# SCRIPPS_new_board.net
KiCad netlist of a schematic drawn in EAGLE
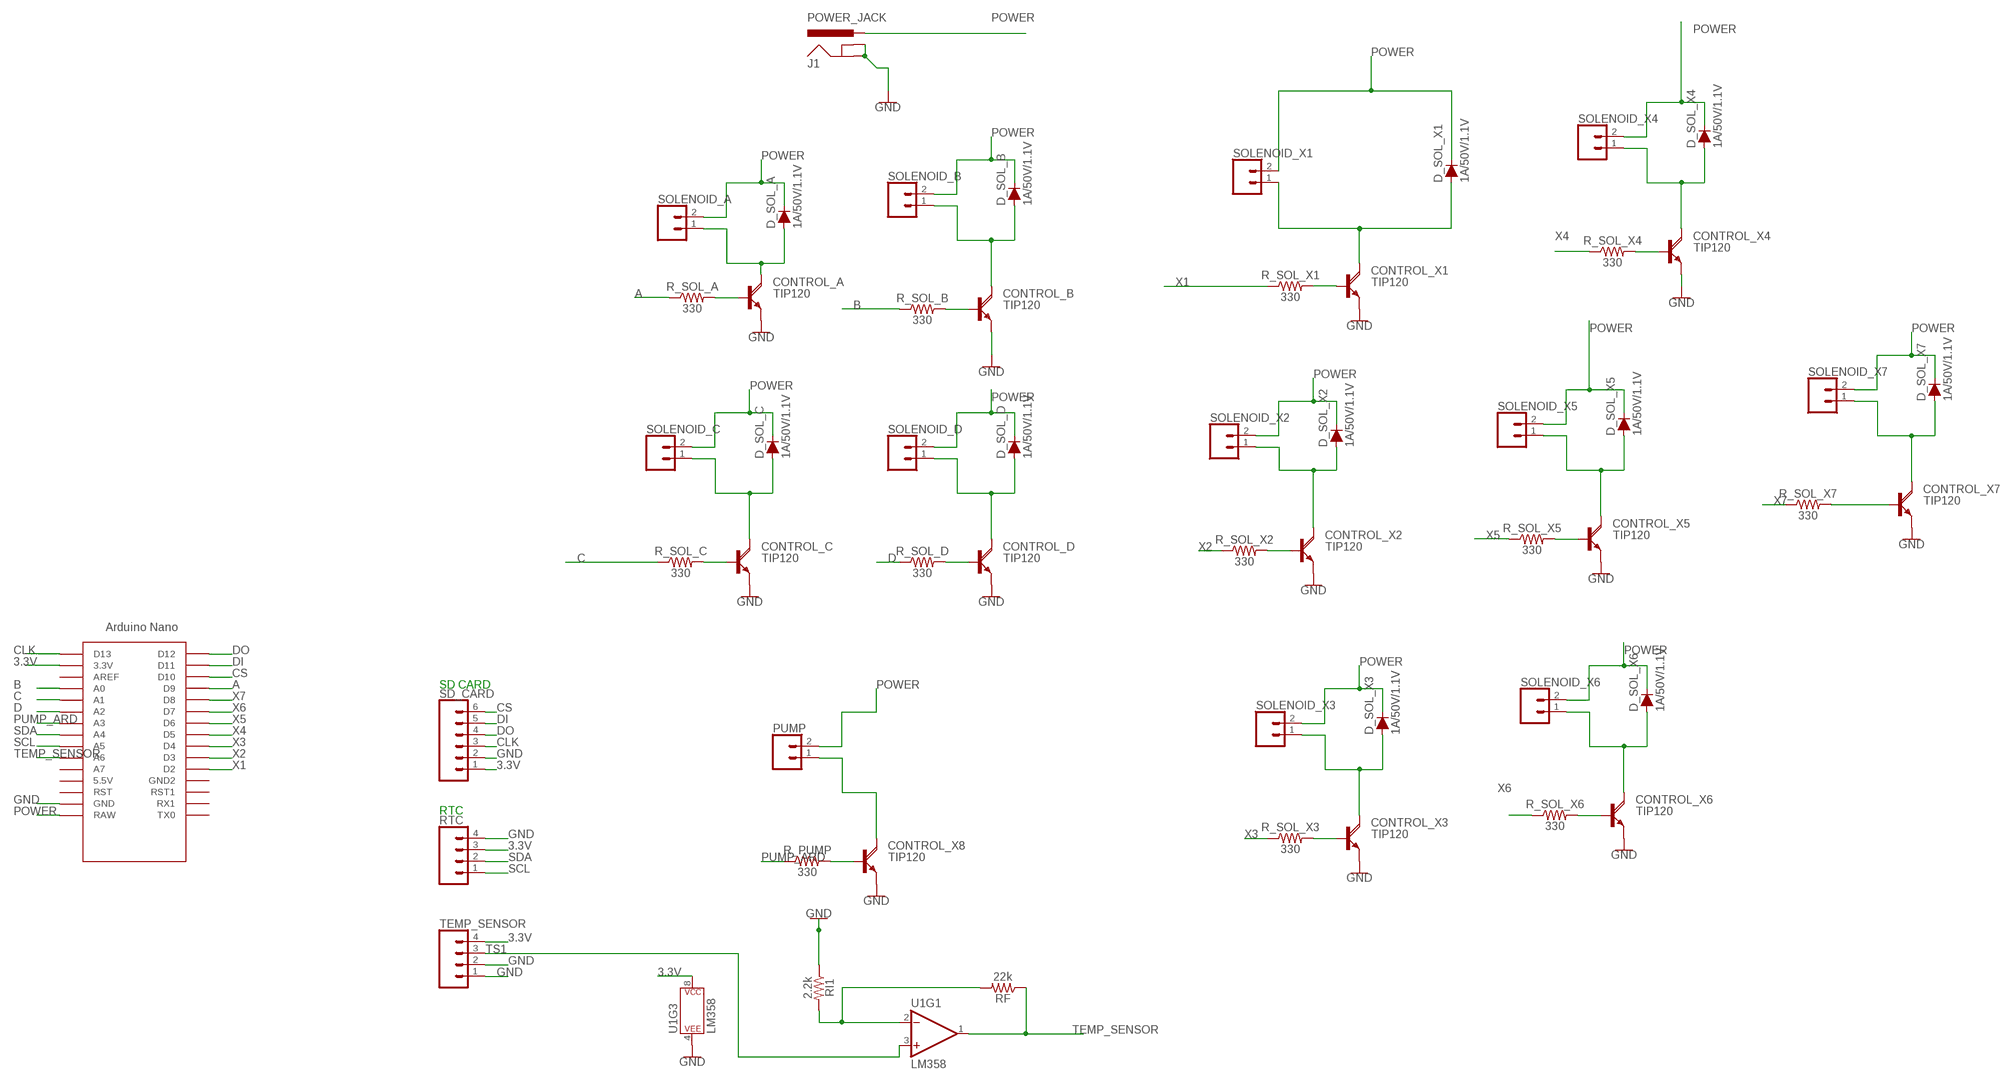
[diagram p0: schematic, sheet 1]

(export (version "E")
  (design (tool "Eeschema 10.0.6"))
  (components
    (comp (ref "CONTROL_A")
      (value "TIP120")
      (footprint "eagle-import:TO220AH")
      (libsource (lib "eagle-import") (part "TIP120"))
    )
    (comp (ref "CONTROL_B")
      (value "TIP120")
      (footprint "eagle-import:TO220AH")
      (libsource (lib "eagle-import") (part "TIP120"))
    )
    (comp (ref "CONTROL_C")
      (value "TIP120")
      (footprint "eagle-import:TO220AH")
      (libsource (lib "eagle-import") (part "TIP120"))
    )
    (comp (ref "CONTROL_D")
      (value "TIP120")
      (footprint "eagle-import:TO220AH")
      (libsource (lib "eagle-import") (part "TIP120"))
    )
    (comp (ref "CONTROL_X1")
      (value "TIP120")
      (footprint "eagle-import:TO220AH")
      (libsource (lib "eagle-import") (part "TIP120"))
    )
    (comp (ref "CONTROL_X2")
      (value "TIP120")
      (footprint "eagle-import:TO220AH")
      (libsource (lib "eagle-import") (part "TIP120"))
    )
    (comp (ref "CONTROL_X3")
      (value "TIP120")
      (footprint "eagle-import:TO220AH")
      (libsource (lib "eagle-import") (part "TIP120"))
    )
    (comp (ref "CONTROL_X4")
      (value "TIP120")
      (footprint "eagle-import:TO220AH")
      (libsource (lib "eagle-import") (part "TIP120"))
    )
    (comp (ref "CONTROL_X5")
      (value "TIP120")
      (footprint "eagle-import:TO220AH")
      (libsource (lib "eagle-import") (part "TIP120"))
    )
    (comp (ref "CONTROL_X6")
      (value "TIP120")
      (footprint "eagle-import:TO220AH")
      (libsource (lib "eagle-import") (part "TIP120"))
    )
    (comp (ref "CONTROL_X7")
      (value "TIP120")
      (footprint "eagle-import:TO220AH")
      (libsource (lib "eagle-import") (part "TIP120"))
    )
    (comp (ref "CONTROL_X8")
      (value "TIP120")
      (footprint "eagle-import:TO220AH")
      (libsource (lib "eagle-import") (part "TIP120"))
    )
    (comp (ref "D_SOL_A")
      (value "1A/50V/1.1V")
      (footprint "eagle-import:DIODE-1N4001")
      (libsource (lib "eagle-import") (part "DIODE-PTH"))
    )
    (comp (ref "D_SOL_B")
      (value "1A/50V/1.1V")
      (footprint "eagle-import:DIODE-1N4001")
      (libsource (lib "eagle-import") (part "DIODE-PTH"))
    )
    (comp (ref "D_SOL_C")
      (value "1A/50V/1.1V")
      (footprint "eagle-import:DIODE-1N4001")
      (libsource (lib "eagle-import") (part "DIODE-PTH"))
    )
    (comp (ref "D_SOL_D")
      (value "1A/50V/1.1V")
      (footprint "eagle-import:DIODE-1N4001")
      (libsource (lib "eagle-import") (part "DIODE-PTH"))
    )
    (comp (ref "D_SOL_X1")
      (value "1A/50V/1.1V")
      (footprint "eagle-import:DIODE-1N4001")
      (libsource (lib "eagle-import") (part "DIODE-PTH"))
    )
    (comp (ref "D_SOL_X2")
      (value "1A/50V/1.1V")
      (footprint "eagle-import:DIODE-1N4001")
      (libsource (lib "eagle-import") (part "DIODE-PTH"))
    )
    (comp (ref "D_SOL_X3")
      (value "1A/50V/1.1V")
      (footprint "eagle-import:DIODE-1N4001")
      (libsource (lib "eagle-import") (part "DIODE-PTH"))
    )
    (comp (ref "D_SOL_X4")
      (value "1A/50V/1.1V")
      (footprint "eagle-import:DIODE-1N4001")
      (libsource (lib "eagle-import") (part "DIODE-PTH"))
    )
    (comp (ref "D_SOL_X5")
      (value "1A/50V/1.1V")
      (footprint "eagle-import:DIODE-1N4001")
      (libsource (lib "eagle-import") (part "DIODE-PTH"))
    )
    (comp (ref "D_SOL_X6")
      (value "1A/50V/1.1V")
      (footprint "eagle-import:DIODE-1N4001")
      (libsource (lib "eagle-import") (part "DIODE-PTH"))
    )
    (comp (ref "D_SOL_X7")
      (value "1A/50V/1.1V")
      (footprint "eagle-import:DIODE-1N4001")
      (libsource (lib "eagle-import") (part "DIODE-PTH"))
    )
    (comp (ref "J1")
      (value "POWER_JACK")
      (footprint "eagle-import:POWER_JACK_PTH")
      (libsource (lib "eagle-import") (part "POWER_JACK"))
    )
    (comp (ref "PUMP")
      (value "CONN_02")
      (footprint "eagle-import:1X02")
      (libsource (lib "eagle-import") (part "CONN_02"))
    )
    (comp (ref "RF")
      (value "22k")
      (footprint "eagle-import:AXIAL-0.3")
      (libsource (lib "eagle-import") (part "330OHM-HORIZ-1/10W-5%"))
    )
    (comp (ref "RI1")
      (value "2.2k")
      (footprint "eagle-import:AXIAL-0.3")
      (libsource (lib "eagle-import") (part "330OHM-HORIZ-1/10W-5%"))
    )
    (comp (ref "RTC")
      (value "CONN_04")
      (footprint "eagle-import:1X04")
      (libsource (lib "eagle-import") (part "CONN_04"))
    )
    (comp (ref "R_PUMP")
      (value "330")
      (footprint "eagle-import:AXIAL-0.3")
      (libsource (lib "eagle-import") (part "330OHM-HORIZ-1/10W-5%"))
    )
    (comp (ref "R_SOL_A")
      (value "330")
      (footprint "eagle-import:AXIAL-0.3")
      (libsource (lib "eagle-import") (part "330OHM-HORIZ-1/10W-5%"))
    )
    (comp (ref "R_SOL_B")
      (value "330")
      (footprint "eagle-import:AXIAL-0.3")
      (libsource (lib "eagle-import") (part "330OHM-HORIZ-1/10W-5%"))
    )
    (comp (ref "R_SOL_C")
      (value "330")
      (footprint "eagle-import:AXIAL-0.3")
      (libsource (lib "eagle-import") (part "330OHM-HORIZ-1/10W-5%"))
    )
    (comp (ref "R_SOL_D")
      (value "330")
      (footprint "eagle-import:AXIAL-0.3")
      (libsource (lib "eagle-import") (part "330OHM-HORIZ-1/10W-5%"))
    )
    (comp (ref "R_SOL_X1")
      (value "330")
      (footprint "eagle-import:AXIAL-0.3")
      (libsource (lib "eagle-import") (part "330OHM-HORIZ-1/10W-5%"))
    )
    (comp (ref "R_SOL_X2")
      (value "330")
      (footprint "eagle-import:AXIAL-0.3")
      (libsource (lib "eagle-import") (part "330OHM-HORIZ-1/10W-5%"))
    )
    (comp (ref "R_SOL_X3")
      (value "330")
      (footprint "eagle-import:AXIAL-0.3")
      (libsource (lib "eagle-import") (part "330OHM-HORIZ-1/10W-5%"))
    )
    (comp (ref "R_SOL_X4")
      (value "330")
      (footprint "eagle-import:AXIAL-0.3")
      (libsource (lib "eagle-import") (part "330OHM-HORIZ-1/10W-5%"))
    )
    (comp (ref "R_SOL_X5")
      (value "330")
      (footprint "eagle-import:AXIAL-0.3")
      (libsource (lib "eagle-import") (part "330OHM-HORIZ-1/10W-5%"))
    )
    (comp (ref "R_SOL_X6")
      (value "330")
      (footprint "eagle-import:AXIAL-0.3")
      (libsource (lib "eagle-import") (part "330OHM-HORIZ-1/10W-5%"))
    )
    (comp (ref "R_SOL_X7")
      (value "330")
      (footprint "eagle-import:AXIAL-0.3")
      (libsource (lib "eagle-import") (part "330OHM-HORIZ-1/10W-5%"))
    )
    (comp (ref "SD_CARD")
      (value "CONN_06FEMALE_LOCK")
      (footprint "eagle-import:1X06_FEMALE_LOCK.010")
      (libsource (lib "eagle-import") (part "CONN_06FEMALE_LOCK"))
    )
    (comp (ref "SOLENOID_A")
      (value "CONN_02")
      (footprint "eagle-import:1X02")
      (libsource (lib "eagle-import") (part "CONN_02"))
    )
    (comp (ref "SOLENOID_B")
      (value "CONN_02")
      (footprint "eagle-import:1X02")
      (libsource (lib "eagle-import") (part "CONN_02"))
    )
    (comp (ref "SOLENOID_C")
      (value "CONN_02")
      (footprint "eagle-import:1X02")
      (libsource (lib "eagle-import") (part "CONN_02"))
    )
    (comp (ref "SOLENOID_D")
      (value "CONN_02")
      (footprint "eagle-import:1X02")
      (libsource (lib "eagle-import") (part "CONN_02"))
    )
    (comp (ref "SOLENOID_X1")
      (value "CONN_02")
      (footprint "eagle-import:1X02")
      (libsource (lib "eagle-import") (part "CONN_02"))
    )
    (comp (ref "SOLENOID_X2")
      (value "CONN_02")
      (footprint "eagle-import:1X02")
      (libsource (lib "eagle-import") (part "CONN_02"))
    )
    (comp (ref "SOLENOID_X3")
      (value "CONN_02")
      (footprint "eagle-import:1X02")
      (libsource (lib "eagle-import") (part "CONN_02"))
    )
    (comp (ref "SOLENOID_X4")
      (value "CONN_02")
      (footprint "eagle-import:1X02")
      (libsource (lib "eagle-import") (part "CONN_02"))
    )
    (comp (ref "SOLENOID_X5")
      (value "CONN_02")
      (footprint "eagle-import:1X02")
      (libsource (lib "eagle-import") (part "CONN_02"))
    )
    (comp (ref "SOLENOID_X6")
      (value "CONN_02")
      (footprint "eagle-import:1X02")
      (libsource (lib "eagle-import") (part "CONN_02"))
    )
    (comp (ref "SOLENOID_X7")
      (value "CONN_02")
      (footprint "eagle-import:1X02")
      (libsource (lib "eagle-import") (part "CONN_02"))
    )
    (comp (ref "TEMP_SENSOR")
      (value "CONN_04")
      (footprint "eagle-import:1X04")
      (libsource (lib "eagle-import") (part "CONN_04"))
    )
    (comp (ref "U$2")
      (value "NANO")
      (footprint "eagle-import:NANO")
      (libsource (lib "eagle-import") (part "NANO"))
    )
    (comp (ref "U1")
      (value "LM358")
      (footprint "eagle-import:DIP08")
      (libsource (lib "eagle-import") (part "LM358"))
    )
  )
  (nets
    (net (code "1") (name "/3.3V") (class "Default")
      (node (ref "RTC") (pin "3") (pinfunction "3_3") (pintype "passive"))
      (node (ref "SD_CARD") (pin "1") (pinfunction "1_1") (pintype "passive"))
      (node (ref "TEMP_SENSOR") (pin "4") (pinfunction "4_4") (pintype "passive"))
      (node (ref "U$2") (pin "3.3V") (pinfunction "3.3V_3.3V") (pintype "bidirectional"))
      (node (ref "U1") (pin "8") (pinfunction "P$V+_8") (pintype "bidirectional"))
    )
    (net (code "2") (name "/A") (class "Default")
      (node (ref "R_SOL_A") (pin "P$1") (pinfunction "1_P$1") (pintype "passive"))
      (node (ref "U$2") (pin "D9") (pinfunction "D9_D9") (pintype "bidirectional"))
    )
    (net (code "3") (name "/B") (class "Default")
      (node (ref "R_SOL_B") (pin "P$1") (pinfunction "1_P$1") (pintype "passive"))
      (node (ref "U$2") (pin "A0") (pinfunction "A0_A0") (pintype "bidirectional"))
    )
    (net (code "4") (name "/C") (class "Default")
      (node (ref "R_SOL_C") (pin "P$1") (pinfunction "1_P$1") (pintype "passive"))
      (node (ref "U$2") (pin "A1") (pinfunction "A1_A1") (pintype "bidirectional"))
    )
    (net (code "5") (name "/CLK") (class "Default")
      (node (ref "SD_CARD") (pin "3") (pinfunction "3_3") (pintype "passive"))
      (node (ref "U$2") (pin "D13") (pinfunction "D13_D13") (pintype "bidirectional"))
    )
    (net (code "6") (name "/CS") (class "Default")
      (node (ref "SD_CARD") (pin "6") (pinfunction "6_6") (pintype "passive"))
      (node (ref "U$2") (pin "D10") (pinfunction "D10_D10") (pintype "bidirectional"))
    )
    (net (code "7") (name "/D") (class "Default")
      (node (ref "R_SOL_D") (pin "P$1") (pinfunction "1_P$1") (pintype "passive"))
      (node (ref "U$2") (pin "A2") (pinfunction "A2_A2") (pintype "bidirectional"))
    )
    (net (code "8") (name "/DI") (class "Default")
      (node (ref "SD_CARD") (pin "5") (pinfunction "5_5") (pintype "passive"))
      (node (ref "U$2") (pin "D11") (pinfunction "D11_D11") (pintype "bidirectional"))
    )
    (net (code "9") (name "/DO") (class "Default")
      (node (ref "SD_CARD") (pin "4") (pinfunction "4_4") (pintype "passive"))
      (node (ref "U$2") (pin "D12") (pinfunction "D12_D12") (pintype "bidirectional"))
    )
    (net (code "10") (name "/POWER") (class "Default")
      (node (ref "D_SOL_A") (pin "C") (pinfunction "C_C") (pintype "passive"))
      (node (ref "D_SOL_B") (pin "C") (pinfunction "C_C") (pintype "passive"))
      (node (ref "D_SOL_C") (pin "C") (pinfunction "C_C") (pintype "passive"))
      (node (ref "D_SOL_D") (pin "C") (pinfunction "C_C") (pintype "passive"))
      (node (ref "D_SOL_X1") (pin "C") (pinfunction "C_C") (pintype "passive"))
      (node (ref "D_SOL_X2") (pin "C") (pinfunction "C_C") (pintype "passive"))
      (node (ref "D_SOL_X3") (pin "C") (pinfunction "C_C") (pintype "passive"))
      (node (ref "D_SOL_X4") (pin "C") (pinfunction "C_C") (pintype "passive"))
      (node (ref "D_SOL_X5") (pin "C") (pinfunction "C_C") (pintype "passive"))
      (node (ref "D_SOL_X6") (pin "C") (pinfunction "C_C") (pintype "passive"))
      (node (ref "D_SOL_X7") (pin "C") (pinfunction "C_C") (pintype "passive"))
      (node (ref "J1") (pin "PWR") (pinfunction "PWR_PWR") (pintype "bidirectional"))
      (node (ref "PUMP") (pin "2") (pinfunction "2_2") (pintype "passive"))
      (node (ref "SOLENOID_A") (pin "2") (pinfunction "2_2") (pintype "passive"))
      (node (ref "SOLENOID_B") (pin "2") (pinfunction "2_2") (pintype "passive"))
      (node (ref "SOLENOID_C") (pin "2") (pinfunction "2_2") (pintype "passive"))
      (node (ref "SOLENOID_D") (pin "2") (pinfunction "2_2") (pintype "passive"))
      (node (ref "SOLENOID_X1") (pin "2") (pinfunction "2_2") (pintype "passive"))
      (node (ref "SOLENOID_X2") (pin "2") (pinfunction "2_2") (pintype "passive"))
      (node (ref "SOLENOID_X3") (pin "2") (pinfunction "2_2") (pintype "passive"))
      (node (ref "SOLENOID_X4") (pin "2") (pinfunction "2_2") (pintype "passive"))
      (node (ref "SOLENOID_X5") (pin "2") (pinfunction "2_2") (pintype "passive"))
      (node (ref "SOLENOID_X6") (pin "2") (pinfunction "2_2") (pintype "passive"))
      (node (ref "SOLENOID_X7") (pin "2") (pinfunction "2_2") (pintype "passive"))
      (node (ref "U$2") (pin "RAW") (pinfunction "RAW_RAW") (pintype "bidirectional"))
    )
    (net (code "11") (name "/PUMP_ARD") (class "Default")
      (node (ref "R_PUMP") (pin "P$1") (pinfunction "1_P$1") (pintype "passive"))
      (node (ref "U$2") (pin "A3") (pinfunction "A3_A3") (pintype "bidirectional"))
    )
    (net (code "12") (name "/SCL") (class "Default")
      (node (ref "RTC") (pin "1") (pinfunction "1_1") (pintype "passive"))
      (node (ref "U$2") (pin "A5") (pinfunction "A5_A5") (pintype "bidirectional"))
    )
    (net (code "13") (name "/SDA") (class "Default")
      (node (ref "RTC") (pin "2") (pinfunction "2_2") (pintype "passive"))
      (node (ref "U$2") (pin "A4") (pinfunction "A4_A4") (pintype "bidirectional"))
    )
    (net (code "14") (name "/TEMP_SENSOR") (class "Default")
      (node (ref "RF") (pin "P$1") (pinfunction "1_P$1") (pintype "passive"))
      (node (ref "U$2") (pin "A6") (pinfunction "A6_A6") (pintype "bidirectional"))
      (node (ref "U1") (pin "1") (pinfunction "OUT_1") (pintype "output"))
    )
    (net (code "15") (name "/TS1") (class "Default")
      (node (ref "TEMP_SENSOR") (pin "3") (pinfunction "3_3") (pintype "passive"))
      (node (ref "U1") (pin "3") (pinfunction "+IN_3") (pintype "input"))
    )
    (net (code "16") (name "/X1") (class "Default")
      (node (ref "R_SOL_X1") (pin "P$1") (pinfunction "1_P$1") (pintype "passive"))
      (node (ref "U$2") (pin "D2") (pinfunction "D2_D2") (pintype "bidirectional"))
    )
    (net (code "17") (name "/X2") (class "Default")
      (node (ref "R_SOL_X2") (pin "P$1") (pinfunction "1_P$1") (pintype "passive"))
      (node (ref "U$2") (pin "D3") (pinfunction "D3_D3") (pintype "bidirectional"))
    )
    (net (code "18") (name "/X3") (class "Default")
      (node (ref "R_SOL_X3") (pin "P$1") (pinfunction "1_P$1") (pintype "passive"))
      (node (ref "U$2") (pin "D4") (pinfunction "D4_D4") (pintype "bidirectional"))
    )
    (net (code "19") (name "/X4") (class "Default")
      (node (ref "R_SOL_X4") (pin "P$1") (pinfunction "1_P$1") (pintype "passive"))
      (node (ref "U$2") (pin "D5") (pinfunction "D5_D5") (pintype "bidirectional"))
    )
    (net (code "20") (name "/X5") (class "Default")
      (node (ref "R_SOL_X5") (pin "P$1") (pinfunction "1_P$1") (pintype "passive"))
      (node (ref "U$2") (pin "D6") (pinfunction "D6_D6") (pintype "bidirectional"))
    )
    (net (code "21") (name "/X6") (class "Default")
      (node (ref "R_SOL_X6") (pin "P$1") (pinfunction "1_P$1") (pintype "passive"))
      (node (ref "U$2") (pin "D7") (pinfunction "D7_D7") (pintype "bidirectional"))
    )
    (net (code "22") (name "/X7") (class "Default")
      (node (ref "R_SOL_X7") (pin "P$1") (pinfunction "1_P$1") (pintype "passive"))
      (node (ref "U$2") (pin "D8") (pinfunction "D8_D8") (pintype "bidirectional"))
    )
    (net (code "23") (name "GND") (class "Default")
      (node (ref "CONTROL_A") (pin "E") (pinfunction "E_E") (pintype "passive"))
      (node (ref "CONTROL_B") (pin "E") (pinfunction "E_E") (pintype "passive"))
      (node (ref "CONTROL_C") (pin "E") (pinfunction "E_E") (pintype "passive"))
      (node (ref "CONTROL_D") (pin "E") (pinfunction "E_E") (pintype "passive"))
      (node (ref "CONTROL_X1") (pin "E") (pinfunction "E_E") (pintype "passive"))
      (node (ref "CONTROL_X2") (pin "E") (pinfunction "E_E") (pintype "passive"))
      (node (ref "CONTROL_X3") (pin "E") (pinfunction "E_E") (pintype "passive"))
      (node (ref "CONTROL_X4") (pin "E") (pinfunction "E_E") (pintype "passive"))
      (node (ref "CONTROL_X5") (pin "E") (pinfunction "E_E") (pintype "passive"))
      (node (ref "CONTROL_X6") (pin "E") (pinfunction "E_E") (pintype "passive"))
      (node (ref "CONTROL_X7") (pin "E") (pinfunction "E_E") (pintype "passive"))
      (node (ref "CONTROL_X8") (pin "E") (pinfunction "E_E") (pintype "passive"))
      (node (ref "J1") (pin "GND") (pinfunction "GND_GND") (pintype "bidirectional"))
      (node (ref "J1") (pin "GNDBREAK") (pinfunction "GNDBREAK_GNDBREAK") (pintype "bidirectional"))
      (node (ref "RI1") (pin "P$1") (pinfunction "1_P$1") (pintype "passive"))
      (node (ref "RTC") (pin "4") (pinfunction "4_4") (pintype "passive"))
      (node (ref "SD_CARD") (pin "2") (pinfunction "2_2") (pintype "passive"))
      (node (ref "TEMP_SENSOR") (pin "1") (pinfunction "1_1") (pintype "passive"))
      (node (ref "TEMP_SENSOR") (pin "2") (pinfunction "2_2") (pintype "passive"))
      (node (ref "U$2") (pin "GND") (pinfunction "GND_GND") (pintype "bidirectional"))
      (node (ref "U1") (pin "4") (pinfunction "P$V-_4") (pintype "bidirectional"))
    )
    (net (code "24") (name "Net-(CONTROL_A-PadC)") (class "Default")
      (node (ref "CONTROL_A") (pin "C") (pinfunction "C_C") (pintype "passive"))
      (node (ref "D_SOL_A") (pin "A") (pinfunction "A_A") (pintype "passive"))
      (node (ref "SOLENOID_A") (pin "1") (pinfunction "1_1") (pintype "passive"))
    )
    (net (code "25") (name "Net-(CONTROL_B-PadC)") (class "Default")
      (node (ref "CONTROL_B") (pin "C") (pinfunction "C_C") (pintype "passive"))
      (node (ref "D_SOL_B") (pin "A") (pinfunction "A_A") (pintype "passive"))
      (node (ref "SOLENOID_B") (pin "1") (pinfunction "1_1") (pintype "passive"))
    )
    (net (code "26") (name "Net-(CONTROL_C-PadC)") (class "Default")
      (node (ref "CONTROL_C") (pin "C") (pinfunction "C_C") (pintype "passive"))
      (node (ref "D_SOL_C") (pin "A") (pinfunction "A_A") (pintype "passive"))
      (node (ref "SOLENOID_C") (pin "1") (pinfunction "1_1") (pintype "passive"))
    )
    (net (code "27") (name "Net-(CONTROL_D-PadC)") (class "Default")
      (node (ref "CONTROL_D") (pin "C") (pinfunction "C_C") (pintype "passive"))
      (node (ref "D_SOL_D") (pin "A") (pinfunction "A_A") (pintype "passive"))
      (node (ref "SOLENOID_D") (pin "1") (pinfunction "1_1") (pintype "passive"))
    )
    (net (code "28") (name "Net-(CONTROL_X1-PadC)") (class "Default")
      (node (ref "CONTROL_X1") (pin "C") (pinfunction "C_C") (pintype "passive"))
      (node (ref "D_SOL_X1") (pin "A") (pinfunction "A_A") (pintype "passive"))
      (node (ref "SOLENOID_X1") (pin "1") (pinfunction "1_1") (pintype "passive"))
    )
    (net (code "29") (name "Net-(CONTROL_X2-PadC)") (class "Default")
      (node (ref "CONTROL_X2") (pin "C") (pinfunction "C_C") (pintype "passive"))
      (node (ref "D_SOL_X2") (pin "A") (pinfunction "A_A") (pintype "passive"))
      (node (ref "SOLENOID_X2") (pin "1") (pinfunction "1_1") (pintype "passive"))
    )
    (net (code "30") (name "Net-(CONTROL_X3-PadC)") (class "Default")
      (node (ref "CONTROL_X3") (pin "C") (pinfunction "C_C") (pintype "passive"))
      (node (ref "D_SOL_X3") (pin "A") (pinfunction "A_A") (pintype "passive"))
      (node (ref "SOLENOID_X3") (pin "1") (pinfunction "1_1") (pintype "passive"))
    )
    (net (code "31") (name "Net-(CONTROL_X4-PadC)") (class "Default")
      (node (ref "CONTROL_X4") (pin "C") (pinfunction "C_C") (pintype "passive"))
      (node (ref "D_SOL_X4") (pin "A") (pinfunction "A_A") (pintype "passive"))
      (node (ref "SOLENOID_X4") (pin "1") (pinfunction "1_1") (pintype "passive"))
    )
    (net (code "32") (name "Net-(CONTROL_X5-PadC)") (class "Default")
      (node (ref "CONTROL_X5") (pin "C") (pinfunction "C_C") (pintype "passive"))
      (node (ref "D_SOL_X5") (pin "A") (pinfunction "A_A") (pintype "passive"))
      (node (ref "SOLENOID_X5") (pin "1") (pinfunction "1_1") (pintype "passive"))
    )
    (net (code "33") (name "Net-(CONTROL_X6-PadC)") (class "Default")
      (node (ref "CONTROL_X6") (pin "C") (pinfunction "C_C") (pintype "passive"))
      (node (ref "D_SOL_X6") (pin "A") (pinfunction "A_A") (pintype "passive"))
      (node (ref "SOLENOID_X6") (pin "1") (pinfunction "1_1") (pintype "passive"))
    )
    (net (code "34") (name "Net-(CONTROL_X7-PadC)") (class "Default")
      (node (ref "CONTROL_X7") (pin "C") (pinfunction "C_C") (pintype "passive"))
      (node (ref "D_SOL_X7") (pin "A") (pinfunction "A_A") (pintype "passive"))
      (node (ref "SOLENOID_X7") (pin "1") (pinfunction "1_1") (pintype "passive"))
    )
    (net (code "35") (name "Net-(CONTROL_X8-PadC)") (class "Default")
      (node (ref "CONTROL_X8") (pin "C") (pinfunction "C_C") (pintype "passive"))
      (node (ref "PUMP") (pin "1") (pinfunction "1_1") (pintype "passive"))
    )
    (net (code "36") (name "Net-(RF-2)") (class "Default")
      (node (ref "RF") (pin "P$2") (pinfunction "2_P$2") (pintype "passive"))
      (node (ref "RI1") (pin "P$2") (pinfunction "2_P$2") (pintype "passive"))
      (node (ref "U1") (pin "2") (pinfunction "-IN_2") (pintype "input"))
    )
    (net (code "37") (name "Net-(R_PUMP-2)") (class "Default")
      (node (ref "CONTROL_X8") (pin "B") (pinfunction "B_B") (pintype "passive"))
      (node (ref "R_PUMP") (pin "P$2") (pinfunction "2_P$2") (pintype "passive"))
    )
    (net (code "38") (name "Net-(R_SOL_A-2)") (class "Default")
      (node (ref "CONTROL_A") (pin "B") (pinfunction "B_B") (pintype "passive"))
      (node (ref "R_SOL_A") (pin "P$2") (pinfunction "2_P$2") (pintype "passive"))
    )
    (net (code "39") (name "Net-(R_SOL_B-2)") (class "Default")
      (node (ref "CONTROL_B") (pin "B") (pinfunction "B_B") (pintype "passive"))
      (node (ref "R_SOL_B") (pin "P$2") (pinfunction "2_P$2") (pintype "passive"))
    )
    (net (code "40") (name "Net-(R_SOL_C-2)") (class "Default")
      (node (ref "CONTROL_C") (pin "B") (pinfunction "B_B") (pintype "passive"))
      (node (ref "R_SOL_C") (pin "P$2") (pinfunction "2_P$2") (pintype "passive"))
    )
    (net (code "41") (name "Net-(R_SOL_D-2)") (class "Default")
      (node (ref "CONTROL_D") (pin "B") (pinfunction "B_B") (pintype "passive"))
      (node (ref "R_SOL_D") (pin "P$2") (pinfunction "2_P$2") (pintype "passive"))
    )
    (net (code "42") (name "Net-(R_SOL_X1-2)") (class "Default")
      (node (ref "CONTROL_X1") (pin "B") (pinfunction "B_B") (pintype "passive"))
      (node (ref "R_SOL_X1") (pin "P$2") (pinfunction "2_P$2") (pintype "passive"))
    )
    (net (code "43") (name "Net-(R_SOL_X2-2)") (class "Default")
      (node (ref "CONTROL_X2") (pin "B") (pinfunction "B_B") (pintype "passive"))
      (node (ref "R_SOL_X2") (pin "P$2") (pinfunction "2_P$2") (pintype "passive"))
    )
    (net (code "44") (name "Net-(R_SOL_X3-2)") (class "Default")
      (node (ref "CONTROL_X3") (pin "B") (pinfunction "B_B") (pintype "passive"))
      (node (ref "R_SOL_X3") (pin "P$2") (pinfunction "2_P$2") (pintype "passive"))
    )
    (net (code "45") (name "Net-(R_SOL_X4-2)") (class "Default")
      (node (ref "CONTROL_X4") (pin "B") (pinfunction "B_B") (pintype "passive"))
      (node (ref "R_SOL_X4") (pin "P$2") (pinfunction "2_P$2") (pintype "passive"))
    )
    (net (code "46") (name "Net-(R_SOL_X5-2)") (class "Default")
      (node (ref "CONTROL_X5") (pin "B") (pinfunction "B_B") (pintype "passive"))
      (node (ref "R_SOL_X5") (pin "P$2") (pinfunction "2_P$2") (pintype "passive"))
    )
    (net (code "47") (name "Net-(R_SOL_X6-2)") (class "Default")
      (node (ref "CONTROL_X6") (pin "B") (pinfunction "B_B") (pintype "passive"))
      (node (ref "R_SOL_X6") (pin "P$2") (pinfunction "2_P$2") (pintype "passive"))
    )
    (net (code "48") (name "Net-(R_SOL_X7-2)") (class "Default")
      (node (ref "CONTROL_X7") (pin "B") (pinfunction "B_B") (pintype "passive"))
      (node (ref "R_SOL_X7") (pin "P$2") (pinfunction "2_P$2") (pintype "passive"))
    )
    (net (code "49") (name "unconnected-(U$2-5.5V-Pad5V)") (class "Default")
      (node (ref "U$2") (pin "5V") (pinfunction "5.5V_5V") (pintype "bidirectional"))
    )
    (net (code "50") (name "unconnected-(U$2-GND2-PadGND1)") (class "Default")
      (node (ref "U$2") (pin "GND1") (pinfunction "GND2_GND1") (pintype "bidirectional"))
    )
    (net (code "51") (name "unconnected-(U$2-PadA7)") (class "Default")
      (node (ref "U$2") (pin "A7") (pinfunction "A7_A7") (pintype "bidirectional"))
    )
    (net (code "52") (name "unconnected-(U$2-PadAREF)") (class "Default")
      (node (ref "U$2") (pin "AREF") (pinfunction "AREF_AREF") (pintype "bidirectional"))
    )
    (net (code "53") (name "unconnected-(U$2-PadICSP1)") (class "Default")
      (node (ref "U$2") (pin "ICSP1") (pinfunction "ICSP1_ICSP1") (pintype "bidirectional"))
    )
    (net (code "54") (name "unconnected-(U$2-PadICSP2)") (class "Default")
      (node (ref "U$2") (pin "ICSP2") (pinfunction "ICSP2_ICSP2") (pintype "bidirectional"))
    )
    (net (code "55") (name "unconnected-(U$2-PadICSP3)") (class "Default")
      (node (ref "U$2") (pin "ICSP3") (pinfunction "ICSP3_ICSP3") (pintype "bidirectional"))
    )
    (net (code "56") (name "unconnected-(U$2-PadICSP4)") (class "Default")
      (node (ref "U$2") (pin "ICSP4") (pinfunction "ICSP4_ICSP4") (pintype "bidirectional"))
    )
    (net (code "57") (name "unconnected-(U$2-PadICSP5)") (class "Default")
      (node (ref "U$2") (pin "ICSP5") (pinfunction "ICSP5_ICSP5") (pintype "bidirectional"))
    )
    (net (code "58") (name "unconnected-(U$2-PadICSP6)") (class "Default")
      (node (ref "U$2") (pin "ICSP6") (pinfunction "ICSP6_ICSP6") (pintype "bidirectional"))
    )
    (net (code "59") (name "unconnected-(U$2-PadRST)") (class "Default")
      (node (ref "U$2") (pin "RST") (pinfunction "RST_RST") (pintype "bidirectional"))
    )
    (net (code "60") (name "unconnected-(U$2-PadRST1)") (class "Default")
      (node (ref "U$2") (pin "RST1") (pinfunction "RST1_RST1") (pintype "bidirectional"))
    )
    (net (code "61") (name "unconnected-(U$2-PadRX1)") (class "Default")
      (node (ref "U$2") (pin "RX1") (pinfunction "RX1_RX1") (pintype "bidirectional"))
    )
    (net (code "62") (name "unconnected-(U$2-PadTX0)") (class "Default")
      (node (ref "U$2") (pin "TX0") (pinfunction "TX0_TX0") (pintype "bidirectional"))
    )
  )
)
